# UT61EWIFI.net
KiCad netlist of a schematic drawn in EAGLE
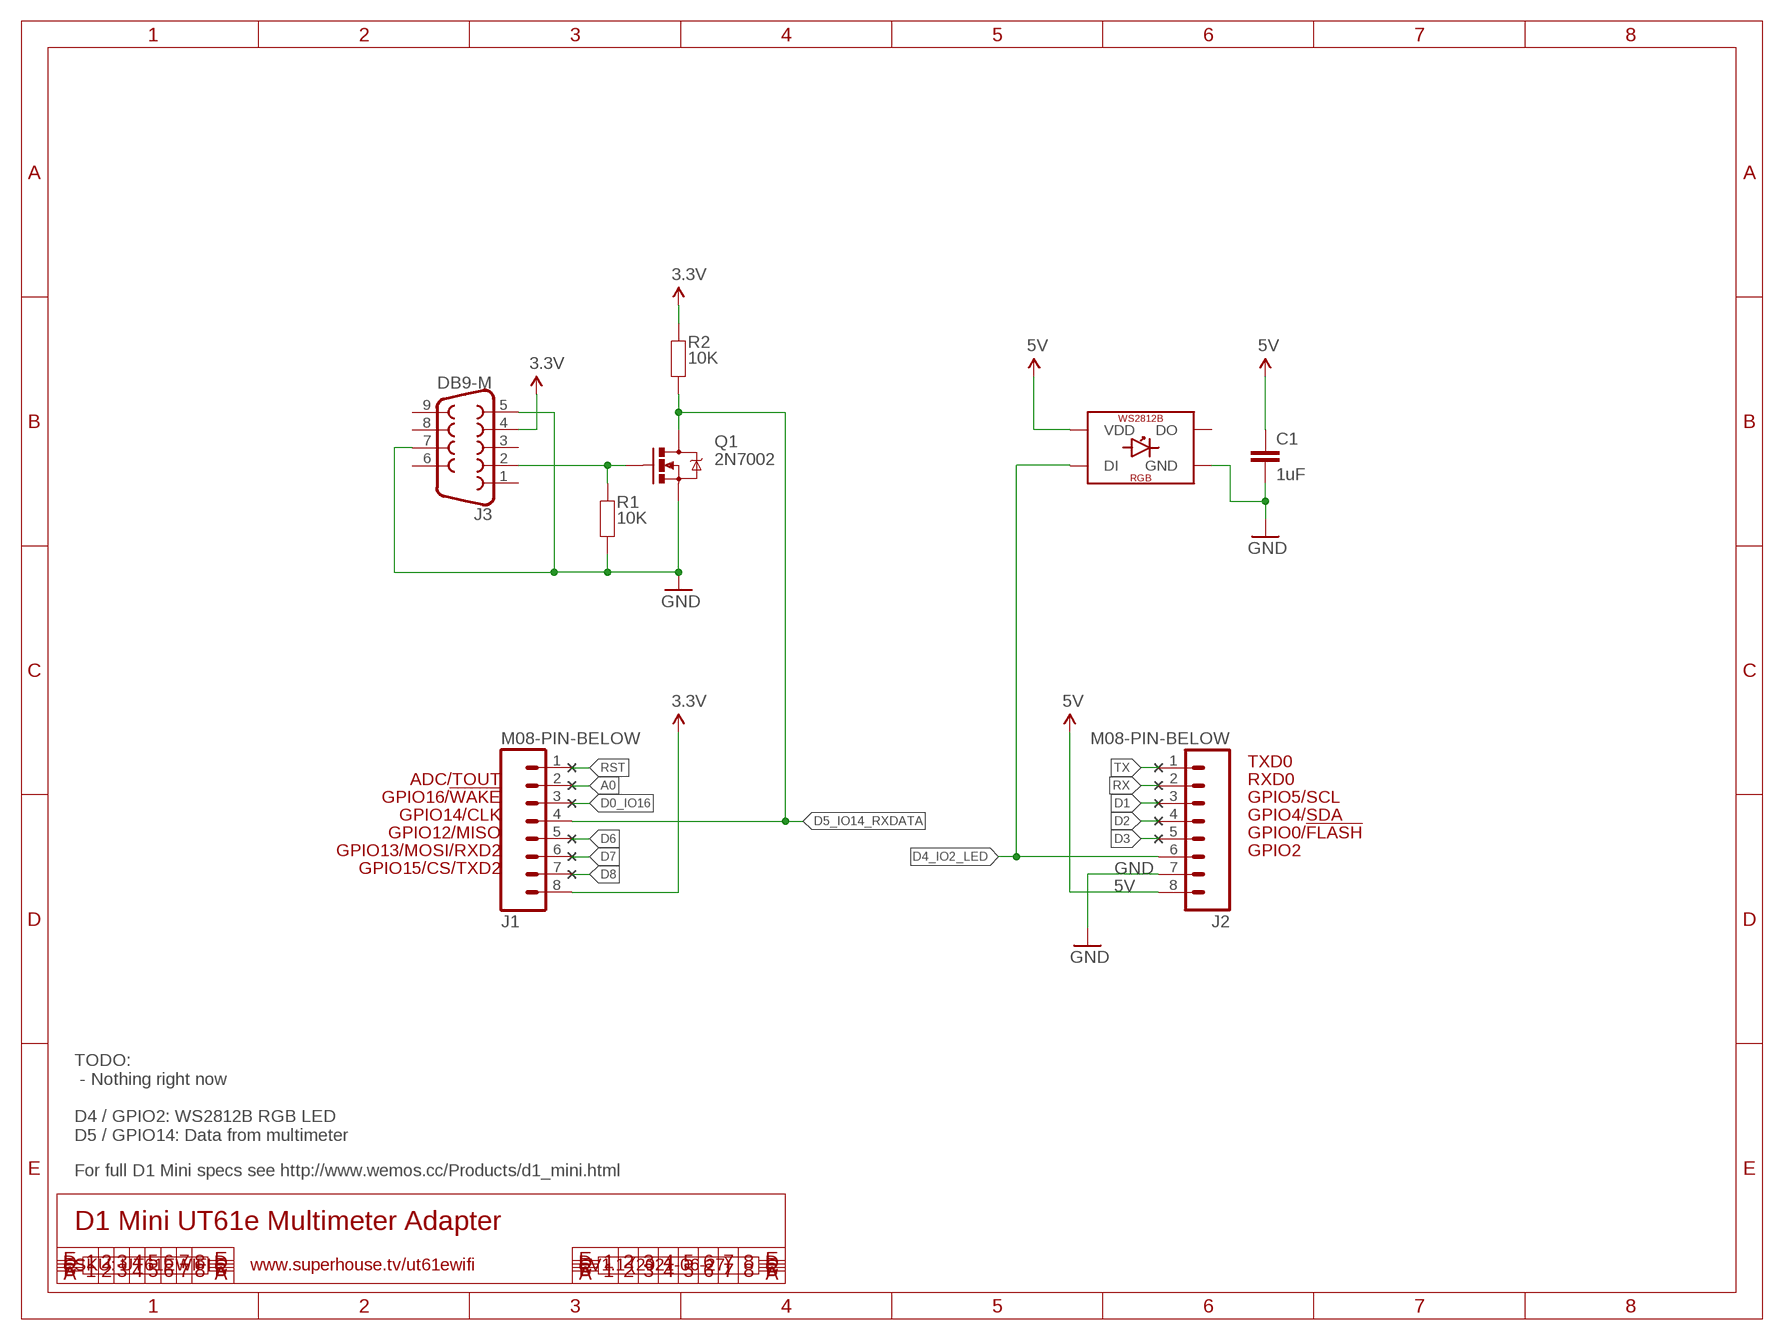
[diagram p0: schematic, sheet 1]

(export (version "E")
  (design (tool "Eeschema 10.0.6"))
  (components
    (comp (ref "C1")
      (value "1uF")
      (footprint "eagle-import:C0603")
      (libsource (lib "eagle-import") (part "CAP0603"))
    )
    (comp (ref "J1")
      (value "M08-PIN-BELOW")
      (footprint "eagle-import:1X08-P-BELOW")
      (libsource (lib "eagle-import") (part "M08-PIN-BELOW"))
    )
    (comp (ref "J2")
      (value "M08-PIN-BELOW")
      (footprint "eagle-import:1X08-P-BELOW")
      (libsource (lib "eagle-import") (part "M08-PIN-BELOW"))
    )
    (comp (ref "J3")
      (value "DB9-M")
      (footprint "eagle-import:DB9-PCB-PLUG")
      (libsource (lib "eagle-import") (part "DB9-PCB-PLUG"))
    )
    (comp (ref "LED1")
      (value "WS2812B")
      (footprint "eagle-import:WS2812B")
      (libsource (lib "eagle-import") (part "WS2812B5050"))
    )
    (comp (ref "Q1")
      (value "2N7002")
      (footprint "eagle-import:SOT23-3")
      (libsource (lib "eagle-import") (part "MOSFET-NCHANNEL-233"))
    )
    (comp (ref "R1")
      (value "10K")
      (footprint "eagle-import:R0603")
      (libsource (lib "eagle-import") (part "RESISTOR0603"))
    )
    (comp (ref "R2")
      (value "10K")
      (footprint "eagle-import:R0603")
      (libsource (lib "eagle-import") (part "RESISTOR0603"))
    )
  )
  (nets
    (net (code "1") (name "3.3V") (class "Default")
      (node (ref "J1") (pin "8") (pinfunction "8_8") (pintype "passive"))
      (node (ref "J3") (pin "4") (pinfunction "4_4") (pintype "passive"))
      (node (ref "R2") (pin "2") (pinfunction "2_2") (pintype "passive"))
    )
    (net (code "2") (name "5V") (class "Default")
      (node (ref "C1") (pin "1") (pinfunction "1_1") (pintype "passive"))
      (node (ref "J2") (pin "8") (pinfunction "8_8") (pintype "passive"))
      (node (ref "LED1") (pin "1-VDD") (pinfunction "VDD_1-VDD") (pintype "power_in"))
    )
    (net (code "3") (name "A0") (class "Default")
      (node (ref "J1") (pin "2") (pinfunction "2_2") (pintype "passive"))
    )
    (net (code "4") (name "D0_IO16") (class "Default")
      (node (ref "J1") (pin "3") (pinfunction "3_3") (pintype "passive"))
    )
    (net (code "5") (name "D1") (class "Default")
      (node (ref "J2") (pin "3") (pinfunction "3_3") (pintype "passive"))
    )
    (net (code "6") (name "D2") (class "Default")
      (node (ref "J2") (pin "4") (pinfunction "4_4") (pintype "passive"))
    )
    (net (code "7") (name "D3") (class "Default")
      (node (ref "J2") (pin "5") (pinfunction "5_5") (pintype "passive"))
    )
    (net (code "8") (name "D4_IO2_LED") (class "Default")
      (node (ref "J2") (pin "6") (pinfunction "6_6") (pintype "passive"))
      (node (ref "LED1") (pin "4-DIN") (pinfunction "DI_4-DIN") (pintype "input"))
    )
    (net (code "9") (name "D5_IO14_RXDATA") (class "Default")
      (node (ref "J1") (pin "4") (pinfunction "4_4") (pintype "passive"))
      (node (ref "Q1") (pin "3") (pinfunction "D_3") (pintype "passive"))
      (node (ref "R2") (pin "1") (pinfunction "1_1") (pintype "passive"))
    )
    (net (code "10") (name "D6") (class "Default")
      (node (ref "J1") (pin "5") (pinfunction "5_5") (pintype "passive"))
    )
    (net (code "11") (name "D7") (class "Default")
      (node (ref "J1") (pin "6") (pinfunction "6_6") (pintype "passive"))
    )
    (net (code "12") (name "D8") (class "Default")
      (node (ref "J1") (pin "7") (pinfunction "7_7") (pintype "passive"))
    )
    (net (code "13") (name "GND") (class "Default")
      (node (ref "C1") (pin "2") (pinfunction "2_2") (pintype "passive"))
      (node (ref "J2") (pin "7") (pinfunction "7_7") (pintype "passive"))
      (node (ref "J3") (pin "5") (pinfunction "5_5") (pintype "passive"))
      (node (ref "J3") (pin "7") (pinfunction "7_7") (pintype "passive"))
      (node (ref "LED1") (pin "3-GND") (pinfunction "GND_3-GND") (pintype "power_in"))
      (node (ref "Q1") (pin "2") (pinfunction "S_2") (pintype "passive"))
      (node (ref "R1") (pin "1") (pinfunction "1_1") (pintype "passive"))
    )
    (net (code "14") (name "Net-(Q1-G)") (class "Default")
      (node (ref "J3") (pin "2") (pinfunction "2_2") (pintype "passive"))
      (node (ref "Q1") (pin "1") (pinfunction "G_1") (pintype "passive"))
      (node (ref "R1") (pin "2") (pinfunction "2_2") (pintype "passive"))
    )
    (net (code "15") (name "RST") (class "Default")
      (node (ref "J1") (pin "1") (pinfunction "1_1") (pintype "passive"))
    )
    (net (code "16") (name "RX") (class "Default")
      (node (ref "J2") (pin "2") (pinfunction "2_2") (pintype "passive"))
    )
    (net (code "17") (name "TX") (class "Default")
      (node (ref "J2") (pin "1") (pinfunction "1_1") (pintype "passive"))
    )
    (net (code "18") (name "unconnected-(J3-Pad1)") (class "Default")
      (node (ref "J3") (pin "1") (pinfunction "1_1") (pintype "passive"))
    )
    (net (code "19") (name "unconnected-(J3-Pad3)") (class "Default")
      (node (ref "J3") (pin "3") (pinfunction "3_3") (pintype "passive"))
    )
    (net (code "20") (name "unconnected-(J3-Pad6)") (class "Default")
      (node (ref "J3") (pin "6") (pinfunction "6_6") (pintype "passive"))
    )
    (net (code "21") (name "unconnected-(J3-Pad8)") (class "Default")
      (node (ref "J3") (pin "8") (pinfunction "8_8") (pintype "passive"))
    )
    (net (code "22") (name "unconnected-(J3-Pad9)") (class "Default")
      (node (ref "J3") (pin "9") (pinfunction "9_9") (pintype "passive"))
    )
    (net (code "23") (name "unconnected-(LED1-DO-Pad2-DOUT)") (class "Default")
      (node (ref "LED1") (pin "2-DOUT") (pinfunction "DO_2-DOUT") (pintype "output"))
    )
  )
)
